# PCB_12V5A_60Wascii.net
KiCad netlist of a schematic drawn in Altium Designer
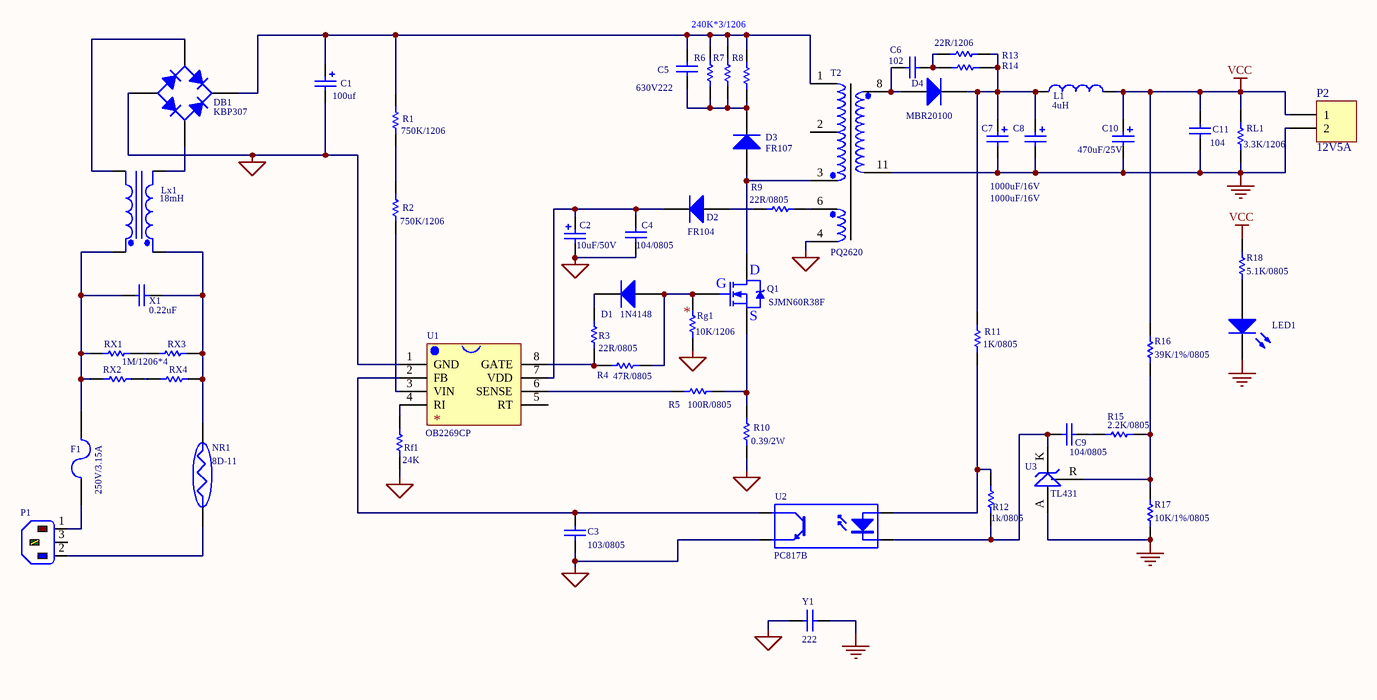
[diagram p0: PCB方案验证板  12V5A 60Wascii.SchDoc]

(export (version "E")
  (design (tool "Eeschema 10.0.6"))
  (components
    (comp (ref "C1")
      (value "100uf")
      (footprint "Cin /400V/56uF Wo")
      (description "Polarized Capacitor (Axial)")
      (fields (field (name "PUBLISHER") "Altium Limited"))
      (libsource (lib "") (part "Cap Pol2_1"))
    )
    (comp (ref "C2")
      (value "10uF/50V")
      (footprint "C Φ5*11 L=2.5")
      (description "Polarized Capacitor (Axial)")
      (fields (field (name "Comment") "47uF/50V") (field (name "PUBLISHER") "Altium Limited"))
      (libsource (lib "") (part "Cap Pol2_1"))
    )
    (comp (ref "C3")
      (value "103/0805")
      (footprint "0805-C")
      (description "Capacitor")
      (fields (field (name "PUBLISHER") "Altium Limited"))
      (libsource (lib "Miscellaneous Devices") (part "Cap"))
    )
    (comp (ref "C4")
      (value "104/0805")
      (footprint "0805-C")
      (description "Capacitor")
      (fields (field (name "PUBLISHER") "Altium Limited"))
      (libsource (lib "Miscellaneous Devices") (part "Cap"))
    )
    (comp (ref "C5")
      (value "630V222")
      (footprint "CBB=7.5MM")
      (description "Capacitor")
      (fields (field (name "PUBLISHER") "Altium Limited"))
      (libsource (lib "Miscellaneous Devices") (part "Cap"))
    )
    (comp (ref "C6")
      (value "102")
      (footprint "1206-C")
      (description "Capacitor")
      (fields (field (name "Comment") "472") (field (name "PUBLISHER") "Altium Limited"))
      (libsource (lib "Miscellaneous Devices") (part "Cap"))
    )
    (comp (ref "C7")
      (value "1000uF/16V")
      (footprint "C 1000UF/16V")
      (description "Polarized Capacitor (Axial)")
      (fields (field (name "PUBLISHER") "Altium Limited"))
      (libsource (lib "Miscellaneous Devices") (part "Cap Pol2"))
    )
    (comp (ref "C8")
      (value "1000uF/16V")
      (footprint "C 1000UF/16V")
      (description "Polarized Capacitor (Axial)")
      (fields (field (name "PUBLISHER") "Altium Limited"))
      (libsource (lib "Miscellaneous Devices") (part "Cap Pol2"))
    )
    (comp (ref "C9")
      (value "104/0805")
      (footprint "0805-C")
      (description "Capacitor")
      (fields (field (name "PUBLISHER") "Altium Limited"))
      (libsource (lib "Miscellaneous Devices") (part "Cap"))
    )
    (comp (ref "C10")
      (value "470uF/25V")
      (footprint "C= 3.5MM 8*15")
      (description "Polarized Capacitor (Axial)")
      (fields (field (name "PUBLISHER") "Altium Limited"))
      (libsource (lib "Miscellaneous Devices") (part "Cap Pol2"))
    )
    (comp (ref "C11")
      (value "104")
      (footprint "1206-C")
      (description "Capacitor")
      (fields (field (name "PUBLISHER") "Altium Limited"))
      (libsource (lib "Miscellaneous Devices") (part "Cap"))
    )
    (comp (ref "D1")
      (value "1N4148")
      (footprint "D 1N4148")
      (description "Silicon Low Leakage Diode")
      (fields (field (name "PUBLISHER") "Altium Limited"))
      (libsource (lib "") (part "Diode BAS116_1"))
    )
    (comp (ref "D2")
      (value "FR104")
      (footprint "D/SOD123")
      (description "Silicon Low Leakage Diode")
      (fields (field (name "PUBLISHER") "Altium Limited"))
      (libsource (lib "Miscellaneous Devices") (part "Diode BAS116"))
    )
    (comp (ref "D3")
      (value "FR107")
      (footprint "D/SOD123")
      (description "Silicon Low Leakage Diode")
      (fields (field (name "PUBLISHER") "Altium Limited"))
      (libsource (lib "Miscellaneous Devices") (part "Diode BAS116"))
    )
    (comp (ref "D4")
      (value "MBR20100")
      (footprint "D TO-220")
      (description "Silicon Low Leakage Diode")
      (fields (field (name "PUBLISHER") "Altium Limited"))
      (libsource (lib "Miscellaneous Devices") (part "Diode BAS116"))
    )
    (comp (ref "DB1")
      (value "KBP307")
      (footprint "DB D=1.1MM")
      (description "Full Wave Diode Bridge")
      (fields (field (name "PUBLISHER") "Altium Limited"))
      (libsource (lib "Miscellaneous Devices") (part "Bridge1"))
    )
    (comp (ref "F1")
      (value "250V/3.15A")
      (footprint "F 3.15A L=5MM")
      (description "Fuse")
      (fields (field (name "PUBLISHER") "Altium Limited"))
      (libsource (lib "Miscellaneous Devices") (part "Fuse 2"))
    )
    (comp (ref "L1")
      (value "4uH")
      (footprint "L=7.6MM")
      (description "Inductor")
      (fields (field (name "PUBLISHER") "Altium Limited"))
      (libsource (lib "Miscellaneous Devices") (part "Inductor"))
    )
    (comp (ref "LED1")
      (value "LED1")
      (footprint "C0805")
      (description "Typical RED, GREEN, YELLOW, AMBER GaAs LED")
      (fields (field (name "PUBLISHER") "Altium Limited"))
      (libsource (lib "Miscellaneous Devices") (part "LED2"))
    )
    (comp (ref "Lx1")
      (value "18mH")
      (footprint "LF=6.9MM")
      (description "Transformer (Ideal)")
      (fields (field (name "PUBLISHER") "Altium Limited"))
      (libsource (lib "Miscellaneous Devices") (part "Trans Ideal"))
    )
    (comp (ref "NR1") (value "8D-11") (footprint "NTC=7.5mm") (libsource (lib "12V5A") (part "NTC")))
    (comp (ref "P1")
      (value "Plug AC Male")
      (footprint "KF128-3.81-2P")
      (description "IEC Mains Power Inlet, EN60 320-1 C14 Class I Cold Condition, PC Flange Rear Mount, Chassis Plug")
      (fields (field (name "PUBLISHER") "Altium Limited"))
      (libsource (lib "Miscellaneous Connectors") (part "Plug AC Male"))
    )
    (comp (ref "P2")
      (value "12V5A")
      (footprint "OUT")
      (description "Header, 2-Pin")
      (fields (field (name "PUBLISHER") "Altium Limited"))
      (libsource (lib "Miscellaneous Connectors") (part "Header 2"))
    )
    (comp (ref "Q1")
      (value "SJMN60R38F")
      (footprint "MOSFET1")
      (description "N-Channel Power MOSFET")
      (fields (field (name "PUBLISHER") "Altium Limited"))
      (libsource (lib "Miscellaneous Devices") (part "NMOS-2"))
    )
    (comp (ref "R1")
      (value "750K/1206")
      (footprint "1206-R")
      (description "Resistor")
      (fields (field (name "PUBLISHER") "Altium Limited"))
      (libsource (lib "Miscellaneous Devices") (part "Res1"))
    )
    (comp (ref "R2")
      (value "750K/1206")
      (footprint "1206-R")
      (description "Resistor")
      (fields (field (name "PUBLISHER") "Altium Limited"))
      (libsource (lib "Miscellaneous Devices") (part "Res1"))
    )
    (comp (ref "R3")
      (value "22R/0805")
      (footprint "0805-R")
      (description "Resistor")
      (fields (field (name "PUBLISHER") "Altium Limited"))
      (libsource (lib "Miscellaneous Devices") (part "Res1"))
    )
    (comp (ref "R4")
      (value "47R/0805")
      (footprint "0805-R")
      (description "Resistor")
      (fields (field (name "PUBLISHER") "Altium Limited"))
      (libsource (lib "Miscellaneous Devices") (part "Res1"))
    )
    (comp (ref "R5")
      (value "100R/0805")
      (footprint "0805-R")
      (description "Resistor")
      (fields (field (name "PUBLISHER") "Altium Limited"))
      (libsource (lib "Miscellaneous Devices") (part "Res1"))
    )
    (comp (ref "R6")
      (value "50K/2510/1W")
      (footprint "1206-R")
      (description "Resistor")
      (fields (field (name "PUBLISHER") "Altium Limited"))
      (libsource (lib "Miscellaneous Devices") (part "Res1"))
    )
    (comp (ref "R7")
      (value "50K/2510/1W")
      (footprint "1206-R")
      (description "Resistor")
      (fields (field (name "PUBLISHER") "Altium Limited"))
      (libsource (lib "Miscellaneous Devices") (part "Res1"))
    )
    (comp (ref "R8")
      (value "50K/2510/1W")
      (footprint "1206-R")
      (description "Resistor")
      (fields (field (name "PUBLISHER") "Altium Limited"))
      (libsource (lib "Miscellaneous Devices") (part "Res1"))
    )
    (comp (ref "R9")
      (value "22R/0805")
      (footprint "0805-R")
      (description "Resistor")
      (fields (field (name "PUBLISHER") "Altium Limited"))
      (libsource (lib "Miscellaneous Devices") (part "Res1"))
    )
    (comp (ref "R10")
      (value "0.39/2W")
      (footprint "R  2W")
      (description "Resistor")
      (fields (field (name "PUBLISHER") "Altium Limited"))
      (libsource (lib "Miscellaneous Devices") (part "Res1"))
    )
    (comp (ref "R11")
      (value "1K/0805")
      (footprint "0805 RC")
      (description "Resistor")
      (fields (field (name "PUBLISHER") "Altium Limited"))
      (libsource (lib "Miscellaneous Devices") (part "Res1"))
    )
    (comp (ref "R12")
      (value "1k/0805")
      (footprint "0805-R")
      (description "Resistor")
      (fields (field (name "PUBLISHER") "Altium Limited"))
      (libsource (lib "Miscellaneous Devices") (part "Res1"))
    )
    (comp (ref "R13")
      (value "51R/1206")
      (footprint "1206-R")
      (description "Resistor")
      (fields (field (name "PUBLISHER") "Altium Limited"))
      (libsource (lib "Miscellaneous Devices") (part "Res1"))
    )
    (comp (ref "R14")
      (value "22R/1206")
      (footprint "1206-R")
      (description "Resistor")
      (fields (field (name "PUBLISHER") "Altium Limited"))
      (libsource (lib "Miscellaneous Devices") (part "Res1"))
    )
    (comp (ref "R15")
      (value "2.2K/0805")
      (footprint "0805-R")
      (description "Resistor")
      (fields (field (name "PUBLISHER") "Altium Limited"))
      (libsource (lib "Miscellaneous Devices") (part "Res1"))
    )
    (comp (ref "R16")
      (value "39K/1%/0805")
      (footprint "0805-R")
      (description "Resistor")
      (fields (field (name "PUBLISHER") "Altium Limited"))
      (libsource (lib "Miscellaneous Devices") (part "Res1"))
    )
    (comp (ref "R17")
      (value "10K/1%/0805")
      (footprint "0805-R")
      (description "Resistor")
      (fields (field (name "Comment") "12.5K/1%/0805") (field (name "PUBLISHER") "Altium Limited"))
      (libsource (lib "Miscellaneous Devices") (part "Res1"))
    )
    (comp (ref "R18")
      (value "5.1K/0805")
      (footprint "0805-R")
      (description "Resistor")
      (fields (field (name "PUBLISHER") "Altium Limited"))
      (libsource (lib "Miscellaneous Devices") (part "Res1"))
    )
    (comp (ref "Rf1")
      (value "24K")
      (footprint "0805-R")
      (description "Resistor")
      (fields (field (name "Comment") "Res1") (field (name "PUBLISHER") "Altium Limited"))
      (libsource (lib "Miscellaneous Devices") (part "Res1"))
    )
    (comp (ref "Rg1")
      (value "10K/1206")
      (footprint "0805-R")
      (description "Resistor")
      (fields (field (name "Comment") "10K/0805") (field (name "PUBLISHER") "Altium Limited"))
      (libsource (lib "Miscellaneous Devices") (part "Res1"))
    )
    (comp (ref "RL1")
      (value "3.3K/1206")
      (footprint "1206-R")
      (description "Resistor")
      (fields (field (name "PUBLISHER") "Altium Limited"))
      (libsource (lib "Miscellaneous Devices") (part "Res1"))
    )
    (comp (ref "RX1")
      (value "1M/1206*4")
      (footprint "1206-R")
      (description "Resistor")
      (fields (field (name "PUBLISHER") "Altium Limited"))
      (libsource (lib "Miscellaneous Devices") (part "Res1"))
    )
    (comp (ref "RX2")
      (value "1M/1206")
      (footprint "1206-R")
      (description "Resistor")
      (fields (field (name "PUBLISHER") "Altium Limited"))
      (libsource (lib "Miscellaneous Devices") (part "Res1"))
    )
    (comp (ref "RX3")
      (value "1M/1206")
      (footprint "1206-R")
      (description "Resistor")
      (fields (field (name "PUBLISHER") "Altium Limited"))
      (libsource (lib "Miscellaneous Devices") (part "Res1"))
    )
    (comp (ref "RX4")
      (value "1M/1206")
      (footprint "1206-R")
      (description "Resistor")
      (fields (field (name "PUBLISHER") "Altium Limited"))
      (libsource (lib "Miscellaneous Devices") (part "Res1"))
    )
    (comp (ref "T2") (value "PQ2620") (footprint "T PQ2620") (libsource (lib "12V5A") (part "T")))
    (comp (ref "U1") (value "OB2269CP") (footprint "OB2269") (libsource (lib "12V5A") (part "OB2269CP")))
    (comp (ref "U2")
      (value "PC817B")
      (footprint "LC-SMD-4")
      (description "4-Pin Phototransistor Optocoupler")
      (fields (field (name "PUBLISHER") "Altium Limited"))
      (libsource (lib "Miscellaneous Devices") (part "Optoisolator1"))
    )
    (comp (ref "U3")
      (value "TL431")
      (footprint "LC-SOT-23(SOT-23-3)")
      (libsource (lib "12V5A") (part "TL431"))
    )
    (comp (ref "X1")
      (value "0.22uF")
      (footprint "CX=10mm")
      (description "Capacitor")
      (fields (field (name "Comment") "224") (field (name "PUBLISHER") "Altium Limited"))
      (libsource (lib "Miscellaneous Devices") (part "Cap"))
    )
    (comp (ref "Y1")
      (value "222")
      (footprint "Y1")
      (description "Capacitor")
      (fields (field (name "PUBLISHER") "Altium Limited"))
      (libsource (lib "Miscellaneous Devices") (part "Cap"))
    )
  )
  (nets
    (net (code "1") (name "GND") (class "Default")
      (node (ref "C10") (pin "1") (pinfunction "1_1") (pintype "passive"))
      (node (ref "C11") (pin "2") (pinfunction "2_2") (pintype "passive"))
      (node (ref "C7") (pin "1") (pinfunction "1_1") (pintype "passive"))
      (node (ref "C8") (pin "1") (pinfunction "1_1") (pintype "passive"))
      (node (ref "LED1") (pin "2") (pinfunction "K_2") (pintype "passive"))
      (node (ref "P2") (pin "GND") (pinfunction "2_GND") (pintype "passive"))
      (node (ref "R17") (pin "1") (pinfunction "1_1") (pintype "passive"))
      (node (ref "RL1") (pin "1") (pinfunction "1_1") (pintype "passive"))
      (node (ref "T2") (pin "11") (pintype "passive"))
      (node (ref "U3") (pin "A") (pinfunction "A_A") (pintype "passive"))
      (node (ref "Y1") (pin "2") (pinfunction "2_2") (pintype "passive"))
    )
    (net (code "2") (name "GND1") (class "Default")
      (node (ref "C1") (pin "2") (pinfunction "2_2") (pintype "passive"))
      (node (ref "C2") (pin "2") (pinfunction "2_2") (pintype "passive"))
      (node (ref "C3") (pin "1") (pinfunction "1_1") (pintype "passive"))
      (node (ref "C4") (pin "2") (pinfunction "2_2") (pintype "passive"))
      (node (ref "DB1") (pin "-") (pinfunction "2_-") (pintype "passive"))
      (node (ref "R10") (pin "1") (pinfunction "1_1") (pintype "passive"))
      (node (ref "Rf1") (pin "2") (pinfunction "2_2") (pintype "passive"))
      (node (ref "Rg1") (pin "2") (pinfunction "2_2") (pintype "passive"))
      (node (ref "T2") (pin "4") (pinfunction "4_4") (pintype "passive"))
      (node (ref "U1") (pin "1") (pinfunction "GND_1") (pintype "passive"))
      (node (ref "U2") (pin "E") (pinfunction "E_E") (pintype "passive"))
      (node (ref "Y1") (pin "1") (pinfunction "1_1") (pintype "passive"))
    )
    (net (code "3") (name "Net-(C6-Pad2)") (class "Default")
      (node (ref "C6") (pin "2") (pinfunction "2_2") (pintype "passive"))
      (node (ref "R13") (pin "2") (pinfunction "2_2") (pintype "passive"))
      (node (ref "R14") (pin "2") (pinfunction "2_2") (pintype "passive"))
    )
    (net (code "4") (name "Net-(C9-Pad1)") (class "Default")
      (node (ref "C9") (pin "1") (pinfunction "1_1") (pintype "passive"))
      (node (ref "R12") (pin "1") (pinfunction "1_1") (pintype "passive"))
      (node (ref "U2") (pin "K") (pinfunction "K_K") (pintype "passive"))
      (node (ref "U3") (pin "K") (pinfunction "K_K") (pintype "passive"))
    )
    (net (code "5") (name "Net-(C9-Pad2)") (class "Default")
      (node (ref "C9") (pin "2") (pinfunction "2_2") (pintype "passive"))
      (node (ref "R15") (pin "2") (pinfunction "2_2") (pintype "passive"))
    )
    (net (code "6") (name "Net-(D1-A)") (class "Default")
      (node (ref "D1") (pin "+") (pinfunction "A_+") (pintype "passive"))
      (node (ref "Q1") (pin "G") (pinfunction "G_G") (pintype "passive"))
      (node (ref "R4") (pin "1") (pinfunction "1_1") (pintype "passive"))
      (node (ref "Rg1") (pin "1") (pinfunction "1_1") (pintype "passive"))
    )
    (net (code "7") (name "Net-(D1-K)") (class "Default")
      (node (ref "D1") (pin "-") (pinfunction "K_-") (pintype "passive"))
      (node (ref "R3") (pin "1") (pinfunction "1_1") (pintype "passive"))
    )
    (net (code "8") (name "Net-(D2-A)") (class "Default")
      (node (ref "D2") (pin "1") (pinfunction "A_1") (pintype "passive"))
      (node (ref "R9") (pin "2") (pinfunction "2_2") (pintype "passive"))
    )
    (net (code "9") (name "Net-(D2-K)") (class "Default")
      (node (ref "C2") (pin "1") (pinfunction "1_1") (pintype "passive"))
      (node (ref "C4") (pin "1") (pinfunction "1_1") (pintype "passive"))
      (node (ref "D2") (pin "2") (pinfunction "K_2") (pintype "passive"))
      (node (ref "U1") (pin "7") (pinfunction "VDD_7") (pintype "passive"))
    )
    (net (code "10") (name "Net-(D3-A)") (class "Default")
      (node (ref "D3") (pin "1") (pinfunction "A_1") (pintype "passive"))
      (node (ref "Q1") (pin "D") (pinfunction "D_D") (pintype "passive"))
      (node (ref "T2") (pin "3") (pintype "passive"))
    )
    (net (code "11") (name "Net-(D3-K)") (class "Default")
      (node (ref "C5") (pin "2") (pinfunction "2_2") (pintype "passive"))
      (node (ref "D3") (pin "2") (pinfunction "K_2") (pintype "passive"))
      (node (ref "R6") (pin "2") (pinfunction "2_2") (pintype "passive"))
      (node (ref "R7") (pin "2") (pinfunction "2_2") (pintype "passive"))
      (node (ref "R8") (pin "2") (pinfunction "2_2") (pintype "passive"))
    )
    (net (code "12") (name "Net-(D4-A)") (class "Default")
      (node (ref "C6") (pin "1") (pinfunction "1_1") (pintype "passive"))
      (node (ref "D4") (pin "1") (pinfunction "A_1") (pintype "passive"))
      (node (ref "T2") (pin "8") (pinfunction "6_8") (pintype "passive"))
    )
    (net (code "13") (name "Net-(D4-K)") (class "Default")
      (node (ref "C7") (pin "2") (pinfunction "2_2") (pintype "passive"))
      (node (ref "C8") (pin "2") (pinfunction "2_2") (pintype "passive"))
      (node (ref "D4") (pin "2") (pinfunction "K_2") (pintype "passive"))
      (node (ref "L1") (pin "1") (pinfunction "1_1") (pintype "passive"))
      (node (ref "R11") (pin "2") (pinfunction "2_2") (pintype "passive"))
      (node (ref "R13") (pin "1") (pinfunction "1_1") (pintype "passive"))
      (node (ref "R14") (pin "1") (pinfunction "1_1") (pintype "passive"))
    )
    (net (code "14") (name "Net-(DB1-1)") (class "Default")
      (node (ref "C1") (pin "1") (pinfunction "1_1") (pintype "passive"))
      (node (ref "C5") (pin "1") (pinfunction "1_1") (pintype "passive"))
      (node (ref "DB1") (pin "+") (pinfunction "1_+") (pintype "passive"))
      (node (ref "R1") (pin "2") (pinfunction "2_2") (pintype "passive"))
      (node (ref "R6") (pin "1") (pinfunction "1_1") (pintype "passive"))
      (node (ref "R7") (pin "1") (pinfunction "1_1") (pintype "passive"))
      (node (ref "R8") (pin "1") (pinfunction "1_1") (pintype "passive"))
      (node (ref "T2") (pin "1") (pintype "passive"))
    )
    (net (code "15") (name "Net-(DB1-3)") (class "Default")
      (node (ref "DB1") (pin "N") (pinfunction "3_N") (pintype "passive"))
      (node (ref "Lx1") (pin "4") (pinfunction "Pri-_4") (pintype "passive"))
    )
    (net (code "16") (name "Net-(DB1-4)") (class "Default")
      (node (ref "DB1") (pin "L") (pinfunction "4_L") (pintype "passive"))
      (node (ref "Lx1") (pin "2") (pinfunction "Sec-_2") (pintype "passive"))
    )
    (net (code "17") (name "Net-(LED1-A)") (class "Default")
      (node (ref "LED1") (pin "1") (pinfunction "A_1") (pintype "passive"))
      (node (ref "R18") (pin "1") (pinfunction "1_1") (pintype "passive"))
    )
    (net (code "18") (name "Net-(Lx1-Pri+)") (class "Default")
      (node (ref "Lx1") (pin "1") (pinfunction "Pri+_1") (pintype "passive"))
      (node (ref "NR1") (pin "1") (pinfunction "1_1") (pintype "passive"))
      (node (ref "RX3") (pin "2") (pinfunction "2_2") (pintype "passive"))
      (node (ref "RX4") (pin "2") (pinfunction "2_2") (pintype "passive"))
      (node (ref "X1") (pin "2") (pinfunction "2_2") (pintype "passive"))
    )
    (net (code "19") (name "Net-(Lx1-Sec+)") (class "Default")
      (node (ref "F1") (pin "2") (pinfunction "2_2") (pintype "passive"))
      (node (ref "Lx1") (pin "3") (pinfunction "Sec+_3") (pintype "passive"))
      (node (ref "RX1") (pin "1") (pinfunction "1_1") (pintype "passive"))
      (node (ref "RX2") (pin "1") (pinfunction "1_1") (pintype "passive"))
      (node (ref "X1") (pin "1") (pinfunction "1_1") (pintype "passive"))
    )
    (net (code "20") (name "Net-(P1-L)") (class "Default")
      (node (ref "F1") (pin "1") (pinfunction "1_1") (pintype "passive"))
      (node (ref "P1") (pin "1") (pinfunction "L_1") (pintype "power_in"))
    )
    (net (code "21") (name "Net-(P1-N)") (class "Default")
      (node (ref "NR1") (pin "2") (pinfunction "2_2") (pintype "passive"))
      (node (ref "P1") (pin "2") (pinfunction "N_2") (pintype "power_in"))
    )
    (net (code "22") (name "Net-(Q1-PadS)") (class "Default")
      (node (ref "Q1") (pin "S") (pinfunction "S_S") (pintype "passive"))
      (node (ref "R10") (pin "2") (pinfunction "2_2") (pintype "passive"))
      (node (ref "R5") (pin "1") (pinfunction "1_1") (pintype "passive"))
    )
    (net (code "23") (name "Net-(R1-Pad1)") (class "Default")
      (node (ref "R1") (pin "1") (pinfunction "1_1") (pintype "passive"))
      (node (ref "R2") (pin "2") (pinfunction "2_2") (pintype "passive"))
    )
    (net (code "24") (name "Net-(R9-Pad1)") (class "Default")
      (node (ref "R9") (pin "1") (pinfunction "1_1") (pintype "passive"))
      (node (ref "T2") (pin "6") (pintype "passive"))
    )
    (net (code "25") (name "Net-(R11-Pad1)") (class "Default")
      (node (ref "R11") (pin "1") (pinfunction "1_1") (pintype "passive"))
      (node (ref "R12") (pin "2") (pinfunction "2_2") (pintype "passive"))
      (node (ref "U2") (pin "A") (pinfunction "A_A") (pintype "passive"))
    )
    (net (code "26") (name "Net-(R15-Pad1)") (class "Default")
      (node (ref "R15") (pin "1") (pinfunction "1_1") (pintype "passive"))
      (node (ref "R16") (pin "1") (pinfunction "1_1") (pintype "passive"))
      (node (ref "R17") (pin "2") (pinfunction "2_2") (pintype "passive"))
      (node (ref "U3") (pin "R") (pinfunction "R_R") (pintype "passive"))
    )
    (net (code "27") (name "Net-(RX1-Pad2)") (class "Default")
      (node (ref "RX1") (pin "2") (pinfunction "2_2") (pintype "passive"))
      (node (ref "RX3") (pin "1") (pinfunction "1_1") (pintype "passive"))
    )
    (net (code "28") (name "Net-(RX2-Pad2)") (class "Default")
      (node (ref "RX2") (pin "2") (pinfunction "2_2") (pintype "passive"))
      (node (ref "RX4") (pin "1") (pinfunction "1_1") (pintype "passive"))
    )
    (net (code "29") (name "Net-(U1-FB)") (class "Default")
      (node (ref "C3") (pin "2") (pinfunction "2_2") (pintype "passive"))
      (node (ref "U1") (pin "2") (pinfunction "FB_2") (pintype "passive"))
      (node (ref "U2") (pin "C") (pinfunction "C_C") (pintype "passive"))
    )
    (net (code "30") (name "Net-(U1-GATE)") (class "Default")
      (node (ref "R3") (pin "2") (pinfunction "2_2") (pintype "passive"))
      (node (ref "R4") (pin "2") (pinfunction "2_2") (pintype "passive"))
      (node (ref "U1") (pin "8") (pinfunction "GATE_8") (pintype "passive"))
    )
    (net (code "31") (name "Net-(U1-RI)") (class "Default")
      (node (ref "Rf1") (pin "1") (pinfunction "1_1") (pintype "passive"))
      (node (ref "U1") (pin "4") (pinfunction "RI_4") (pintype "passive"))
    )
    (net (code "32") (name "Net-(U1-SENSE)") (class "Default")
      (node (ref "R5") (pin "2") (pinfunction "2_2") (pintype "passive"))
      (node (ref "U1") (pin "6") (pinfunction "SENSE_6") (pintype "passive"))
    )
    (net (code "33") (name "Net-(U1-VIN)") (class "Default")
      (node (ref "R2") (pin "1") (pinfunction "1_1") (pintype "passive"))
      (node (ref "U1") (pin "3") (pinfunction "VIN_3") (pintype "passive"))
    )
    (net (code "34") (name "VCC") (class "Default")
      (node (ref "C10") (pin "2") (pinfunction "2_2") (pintype "passive"))
      (node (ref "C11") (pin "1") (pinfunction "1_1") (pintype "passive"))
      (node (ref "L1") (pin "2") (pinfunction "2_2") (pintype "passive"))
      (node (ref "P2") (pin "VCC") (pinfunction "1_VCC") (pintype "passive"))
      (node (ref "R16") (pin "2") (pinfunction "2_2") (pintype "passive"))
      (node (ref "R18") (pin "2") (pinfunction "2_2") (pintype "passive"))
      (node (ref "RL1") (pin "2") (pinfunction "2_2") (pintype "passive"))
    )
    (net (code "35") (name "unconnected-(P1-E-Pad3)") (class "Default")
      (node (ref "P1") (pin "3") (pinfunction "E_3") (pintype "power_in"))
    )
    (net (code "36") (name "unconnected-(T2-Pad2)") (class "Default")
      (node (ref "T2") (pin "2") (pintype "passive"))
    )
    (net (code "37") (name "unconnected-(U1-RT-Pad5)") (class "Default")
      (node (ref "U1") (pin "5") (pinfunction "RT_5") (pintype "passive"))
    )
  )
)
